# HBridge.net
KiCad netlist of a schematic drawn in Altium Designer
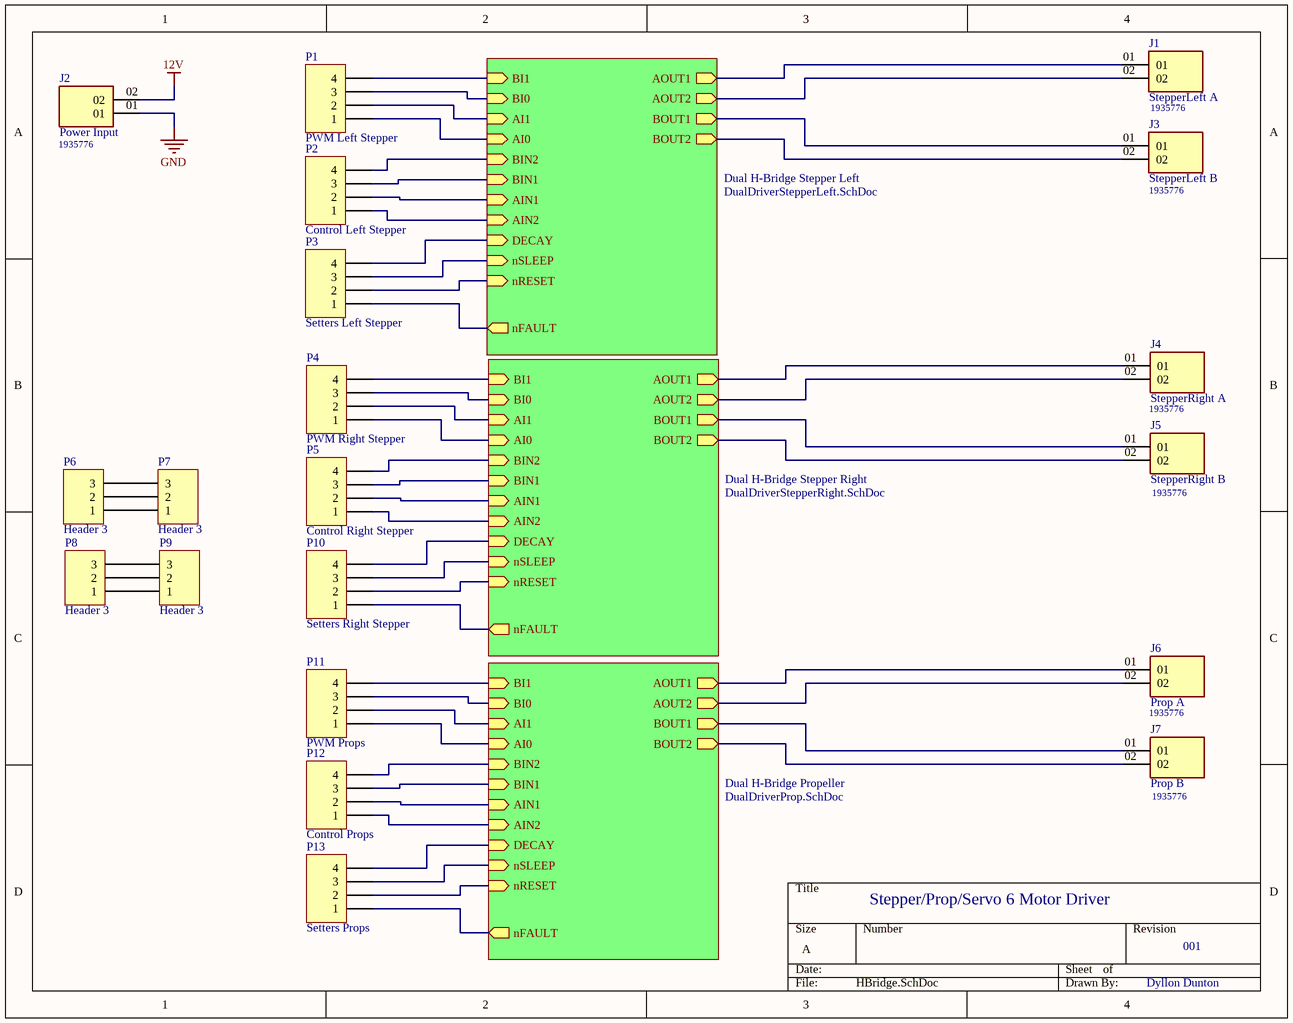
[diagram p0: HBridge.SchDoc]

(export (version "E")
  (design (tool "Eeschema 10.0.6"))
  (components
    (comp (ref "J1")
      (value "StepperLeft A")
      (footprint "PHOENIX_1935776")
      (fields (field (name "MP") "1935776"))
      (libsource (lib "1935776") (part "1935776"))
    )
    (comp (ref "J2")
      (value "Power Input")
      (footprint "PHOENIX_1935776")
      (fields (field (name "MP") "1935776"))
      (libsource (lib "") (part "1935776_1"))
    )
    (comp (ref "J3")
      (value "StepperLeft B")
      (footprint "PHOENIX_1935776")
      (fields (field (name "MP") "1935776"))
      (libsource (lib "1935776") (part "1935776"))
    )
    (comp (ref "J4")
      (value "StepperRight A")
      (footprint "PHOENIX_1935776")
      (fields (field (name "MP") "1935776"))
      (libsource (lib "1935776") (part "1935776"))
    )
    (comp (ref "J5")
      (value "StepperRight B")
      (footprint "PHOENIX_1935776")
      (fields (field (name "MP") "1935776"))
      (libsource (lib "1935776") (part "1935776"))
    )
    (comp (ref "J6")
      (value "Prop A")
      (footprint "PHOENIX_1935776")
      (fields (field (name "MP") "1935776"))
      (libsource (lib "1935776") (part "1935776"))
    )
    (comp (ref "J7")
      (value "Prop B")
      (footprint "PHOENIX_1935776")
      (fields (field (name "MP") "1935776"))
      (libsource (lib "1935776") (part "1935776"))
    )
    (comp (ref "P1")
      (value "PWM Left Stepper")
      (footprint "HDR1X4")
      (description "Header, 4-Pin")
      (fields (field (name "PUBLISHER") "Altium Limited"))
      (libsource (lib "Miscellaneous Connectors") (part "Header 4"))
    )
    (comp (ref "P2")
      (value "Control Left Stepper")
      (footprint "HDR1X4")
      (description "Header, 4-Pin")
      (fields (field (name "PUBLISHER") "Altium Limited"))
      (libsource (lib "Miscellaneous Connectors") (part "Header 4"))
    )
    (comp (ref "P3")
      (value "Setters Left Stepper")
      (footprint "HDR1X4")
      (description "Header, 4-Pin")
      (fields (field (name "PUBLISHER") "Altium Limited"))
      (libsource (lib "Miscellaneous Connectors") (part "Header 4"))
    )
    (comp (ref "P4")
      (value "PWM Right Stepper")
      (footprint "HDR1X4")
      (description "Header, 4-Pin")
      (fields (field (name "PUBLISHER") "Altium Limited"))
      (libsource (lib "Miscellaneous Connectors") (part "Header 4"))
    )
    (comp (ref "P5")
      (value "Control Right Stepper")
      (footprint "HDR1X4")
      (description "Header, 4-Pin")
      (fields (field (name "PUBLISHER") "Altium Limited"))
      (libsource (lib "Miscellaneous Connectors") (part "Header 4"))
    )
    (comp (ref "P6")
      (value "Header 3")
      (footprint "HDR1X3")
      (description "Header, 3-Pin")
      (fields (field (name "PUBLISHER") "Altium Limited"))
      (libsource (lib "") (part "Header 3_1"))
    )
    (comp (ref "P7")
      (value "Header 3")
      (footprint "HDR1X3")
      (description "Header, 3-Pin")
      (fields (field (name "PUBLISHER") "Altium Limited"))
      (libsource (lib "Miscellaneous Connectors") (part "Header 3"))
    )
    (comp (ref "P8")
      (value "Header 3")
      (footprint "HDR1X3")
      (description "Header, 3-Pin")
      (fields (field (name "PUBLISHER") "Altium Limited"))
      (libsource (lib "") (part "Header 3_1"))
    )
    (comp (ref "P9")
      (value "Header 3")
      (footprint "HDR1X3")
      (description "Header, 3-Pin")
      (fields (field (name "PUBLISHER") "Altium Limited"))
      (libsource (lib "Miscellaneous Connectors") (part "Header 3"))
    )
    (comp (ref "P10")
      (value "Setters Right Stepper")
      (footprint "HDR1X4")
      (description "Header, 4-Pin")
      (fields (field (name "PUBLISHER") "Altium Limited"))
      (libsource (lib "Miscellaneous Connectors") (part "Header 4"))
    )
    (comp (ref "P11")
      (value "PWM Props")
      (footprint "HDR1X4")
      (description "Header, 4-Pin")
      (fields (field (name "PUBLISHER") "Altium Limited"))
      (libsource (lib "Miscellaneous Connectors") (part "Header 4"))
    )
    (comp (ref "P12")
      (value "Control Props")
      (footprint "HDR1X4")
      (description "Header, 4-Pin")
      (fields (field (name "PUBLISHER") "Altium Limited"))
      (libsource (lib "Miscellaneous Connectors") (part "Header 4"))
    )
    (comp (ref "P13")
      (value "Setters Props")
      (footprint "HDR1X4")
      (description "Header, 4-Pin")
      (fields (field (name "PUBLISHER") "Altium Limited"))
      (libsource (lib "Miscellaneous Connectors") (part "Header 4"))
    )
  )
  (nets
    (net (code "1") (name "/AI0") (class "Default")
      (node (ref "P11") (pin "1") (pinfunction "1_1") (pintype "passive"))
    )
    (net (code "2") (name "/AI0_1") (class "Default")
      (node (ref "P1") (pin "1") (pinfunction "1_1") (pintype "passive"))
    )
    (net (code "3") (name "/AI0_2") (class "Default")
      (node (ref "P4") (pin "1") (pinfunction "1_1") (pintype "passive"))
    )
    (net (code "4") (name "/AI1") (class "Default")
      (node (ref "P4") (pin "2") (pinfunction "2_2") (pintype "passive"))
    )
    (net (code "5") (name "/AI1_1") (class "Default")
      (node (ref "P1") (pin "2") (pinfunction "2_2") (pintype "passive"))
    )
    (net (code "6") (name "/AI1_2") (class "Default")
      (node (ref "P11") (pin "2") (pinfunction "2_2") (pintype "passive"))
    )
    (net (code "7") (name "/AIN1") (class "Default")
      (node (ref "P5") (pin "2") (pinfunction "2_2") (pintype "passive"))
    )
    (net (code "8") (name "/AIN1_1") (class "Default")
      (node (ref "P2") (pin "2") (pinfunction "2_2") (pintype "passive"))
    )
    (net (code "9") (name "/AIN1_2") (class "Default")
      (node (ref "P12") (pin "2") (pinfunction "2_2") (pintype "passive"))
    )
    (net (code "10") (name "/AIN2") (class "Default")
      (node (ref "P5") (pin "1") (pinfunction "1_1") (pintype "passive"))
    )
    (net (code "11") (name "/AIN2_1") (class "Default")
      (node (ref "P2") (pin "1") (pinfunction "1_1") (pintype "passive"))
    )
    (net (code "12") (name "/AIN2_2") (class "Default")
      (node (ref "P12") (pin "1") (pinfunction "1_1") (pintype "passive"))
    )
    (net (code "13") (name "/AOUT1") (class "Default")
      (node (ref "J6") (pin "01") (pinfunction "01_01") (pintype "passive"))
    )
    (net (code "14") (name "/AOUT1_1") (class "Default")
      (node (ref "J4") (pin "01") (pinfunction "01_01") (pintype "passive"))
    )
    (net (code "15") (name "/AOUT1_2") (class "Default")
      (node (ref "J1") (pin "01") (pinfunction "01_01") (pintype "passive"))
    )
    (net (code "16") (name "/AOUT2") (class "Default")
      (node (ref "J6") (pin "02") (pinfunction "02_02") (pintype "passive"))
    )
    (net (code "17") (name "/AOUT2_1") (class "Default")
      (node (ref "J4") (pin "02") (pinfunction "02_02") (pintype "passive"))
    )
    (net (code "18") (name "/AOUT2_2") (class "Default")
      (node (ref "J1") (pin "02") (pinfunction "02_02") (pintype "passive"))
    )
    (net (code "19") (name "/BI0") (class "Default")
      (node (ref "P4") (pin "3") (pinfunction "3_3") (pintype "passive"))
    )
    (net (code "20") (name "/BI0_1") (class "Default")
      (node (ref "P1") (pin "3") (pinfunction "3_3") (pintype "passive"))
    )
    (net (code "21") (name "/BI0_2") (class "Default")
      (node (ref "P11") (pin "3") (pinfunction "3_3") (pintype "passive"))
    )
    (net (code "22") (name "/BI1") (class "Default")
      (node (ref "P11") (pin "4") (pinfunction "4_4") (pintype "passive"))
    )
    (net (code "23") (name "/BI1_1") (class "Default")
      (node (ref "P1") (pin "4") (pinfunction "4_4") (pintype "passive"))
    )
    (net (code "24") (name "/BI1_2") (class "Default")
      (node (ref "P4") (pin "4") (pinfunction "4_4") (pintype "passive"))
    )
    (net (code "25") (name "/BIN1") (class "Default")
      (node (ref "P5") (pin "3") (pinfunction "3_3") (pintype "passive"))
    )
    (net (code "26") (name "/BIN1_1") (class "Default")
      (node (ref "P2") (pin "3") (pinfunction "3_3") (pintype "passive"))
    )
    (net (code "27") (name "/BIN1_2") (class "Default")
      (node (ref "P12") (pin "3") (pinfunction "3_3") (pintype "passive"))
    )
    (net (code "28") (name "/BIN2") (class "Default")
      (node (ref "P5") (pin "4") (pinfunction "4_4") (pintype "passive"))
    )
    (net (code "29") (name "/BIN2_1") (class "Default")
      (node (ref "P2") (pin "4") (pinfunction "4_4") (pintype "passive"))
    )
    (net (code "30") (name "/BIN2_2") (class "Default")
      (node (ref "P12") (pin "4") (pinfunction "4_4") (pintype "passive"))
    )
    (net (code "31") (name "/BOUT1") (class "Default")
      (node (ref "J7") (pin "01") (pinfunction "01_01") (pintype "passive"))
    )
    (net (code "32") (name "/BOUT1_1") (class "Default")
      (node (ref "J5") (pin "01") (pinfunction "01_01") (pintype "passive"))
    )
    (net (code "33") (name "/BOUT1_2") (class "Default")
      (node (ref "J3") (pin "01") (pinfunction "01_01") (pintype "passive"))
    )
    (net (code "34") (name "/BOUT2") (class "Default")
      (node (ref "J7") (pin "02") (pinfunction "02_02") (pintype "passive"))
    )
    (net (code "35") (name "/BOUT2_1") (class "Default")
      (node (ref "J5") (pin "02") (pinfunction "02_02") (pintype "passive"))
    )
    (net (code "36") (name "/BOUT2_2") (class "Default")
      (node (ref "J3") (pin "02") (pinfunction "02_02") (pintype "passive"))
    )
    (net (code "37") (name "/DECAY") (class "Default")
      (node (ref "P10") (pin "4") (pinfunction "4_4") (pintype "passive"))
    )
    (net (code "38") (name "/DECAY_1") (class "Default")
      (node (ref "P13") (pin "4") (pinfunction "4_4") (pintype "passive"))
    )
    (net (code "39") (name "/DECAY_2") (class "Default")
      (node (ref "P3") (pin "4") (pinfunction "4_4") (pintype "passive"))
    )
    (net (code "40") (name "/nFAULT") (class "Default")
      (node (ref "P3") (pin "1") (pinfunction "1_1") (pintype "passive"))
    )
    (net (code "41") (name "/nFAULT_1") (class "Default")
      (node (ref "P13") (pin "1") (pinfunction "1_1") (pintype "passive"))
    )
    (net (code "42") (name "/nFAULT_2") (class "Default")
      (node (ref "P10") (pin "1") (pinfunction "1_1") (pintype "passive"))
    )
    (net (code "43") (name "/nRESET") (class "Default")
      (node (ref "P3") (pin "2") (pinfunction "2_2") (pintype "passive"))
    )
    (net (code "44") (name "/nRESET_1") (class "Default")
      (node (ref "P13") (pin "2") (pinfunction "2_2") (pintype "passive"))
    )
    (net (code "45") (name "/nRESET_2") (class "Default")
      (node (ref "P10") (pin "2") (pinfunction "2_2") (pintype "passive"))
    )
    (net (code "46") (name "/nSLEEP") (class "Default")
      (node (ref "P10") (pin "3") (pinfunction "3_3") (pintype "passive"))
    )
    (net (code "47") (name "/nSLEEP_1") (class "Default")
      (node (ref "P13") (pin "3") (pinfunction "3_3") (pintype "passive"))
    )
    (net (code "48") (name "/nSLEEP_2") (class "Default")
      (node (ref "P3") (pin "3") (pinfunction "3_3") (pintype "passive"))
    )
    (net (code "49") (name "12V") (class "Default")
      (node (ref "J2") (pin "02") (pinfunction "02_02") (pintype "passive"))
    )
    (net (code "50") (name "GND") (class "Default")
      (node (ref "J2") (pin "01") (pinfunction "01_01") (pintype "passive"))
    )
    (net (code "51") (name "Net-(P6-Pad1)") (class "Default")
      (node (ref "P6") (pin "1") (pinfunction "1_1") (pintype "passive"))
      (node (ref "P7") (pin "1") (pinfunction "1_1") (pintype "passive"))
    )
    (net (code "52") (name "Net-(P6-Pad2)") (class "Default")
      (node (ref "P6") (pin "2") (pinfunction "2_2") (pintype "passive"))
      (node (ref "P7") (pin "2") (pinfunction "2_2") (pintype "passive"))
    )
    (net (code "53") (name "Net-(P6-Pad3)") (class "Default")
      (node (ref "P6") (pin "3") (pinfunction "3_3") (pintype "passive"))
      (node (ref "P7") (pin "3") (pinfunction "3_3") (pintype "passive"))
    )
    (net (code "54") (name "Net-(P8-Pad1)") (class "Default")
      (node (ref "P8") (pin "1") (pinfunction "1_1") (pintype "passive"))
      (node (ref "P9") (pin "1") (pinfunction "1_1") (pintype "passive"))
    )
    (net (code "55") (name "Net-(P8-Pad2)") (class "Default")
      (node (ref "P8") (pin "2") (pinfunction "2_2") (pintype "passive"))
      (node (ref "P9") (pin "2") (pinfunction "2_2") (pintype "passive"))
    )
    (net (code "56") (name "Net-(P8-Pad3)") (class "Default")
      (node (ref "P8") (pin "3") (pinfunction "3_3") (pintype "passive"))
      (node (ref "P9") (pin "3") (pinfunction "3_3") (pintype "passive"))
    )
  )
)
